# CH1_CH2.net
KiCad netlist of a schematic drawn in Altium Designer
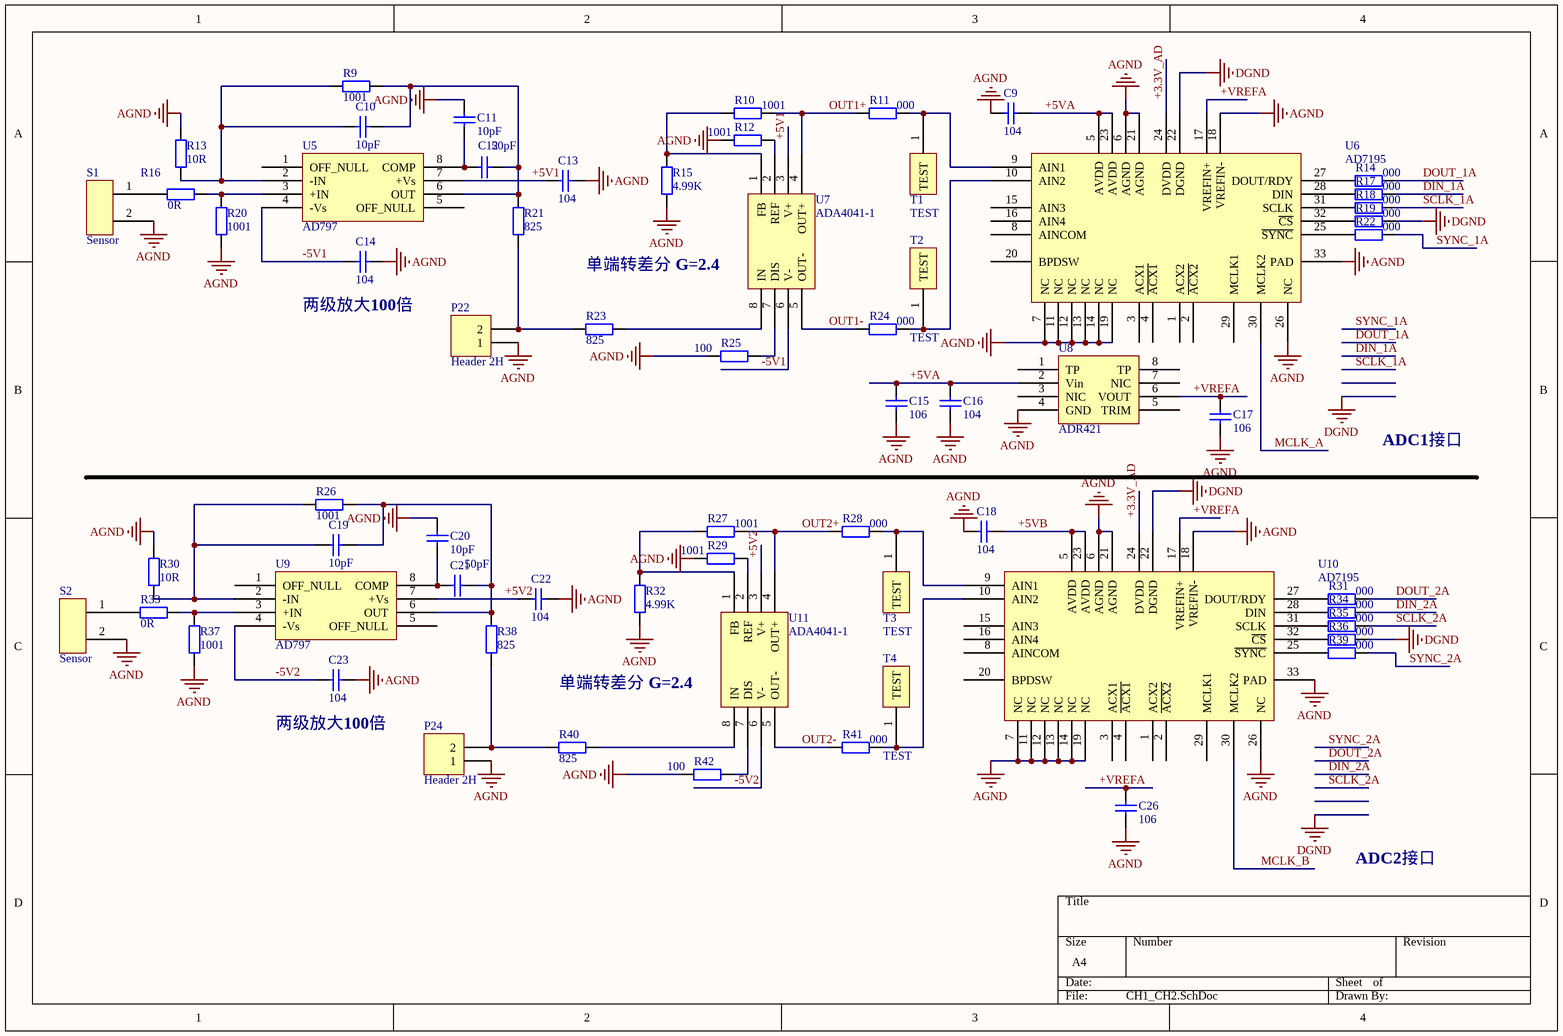
[diagram p0: CH1_CH2.SchDoc]

(export (version "E")
  (design (tool "Eeschema 10.0.6"))
  (components
    (comp (ref "C9")
      (value "104")
      (footprint "0603")
      (description "Capacitor")
      (fields (field (name "PUBLISHER") "Altium Limited"))
      (libsource (lib "Miscellaneous Devices") (part "Cap"))
    )
    (comp (ref "C10")
      (value "10pF")
      (footprint "0603")
      (description "Capacitor")
      (fields (field (name "PUBLISHER") "Altium Limited"))
      (libsource (lib "Miscellaneous Devices") (part "Cap"))
    )
    (comp (ref "C11")
      (value "10pF")
      (footprint "0603")
      (description "Capacitor")
      (fields (field (name "PUBLISHER") "Altium Limited"))
      (libsource (lib "Miscellaneous Devices") (part "Cap"))
    )
    (comp (ref "C12")
      (value "50pF")
      (footprint "0603")
      (description "Capacitor")
      (fields (field (name "PUBLISHER") "Altium Limited"))
      (libsource (lib "Miscellaneous Devices") (part "Cap"))
    )
    (comp (ref "C13")
      (value "104")
      (footprint "0603")
      (description "Capacitor")
      (fields (field (name "PUBLISHER") "Altium Limited"))
      (libsource (lib "Miscellaneous Devices") (part "Cap"))
    )
    (comp (ref "C14")
      (value "104")
      (footprint "0603")
      (description "Capacitor")
      (fields (field (name "PUBLISHER") "Altium Limited"))
      (libsource (lib "Miscellaneous Devices") (part "Cap"))
    )
    (comp (ref "C15")
      (value "106")
      (footprint "0603")
      (description "Capacitor")
      (fields (field (name "PUBLISHER") "Altium Limited"))
      (libsource (lib "Miscellaneous Devices") (part "Cap"))
    )
    (comp (ref "C16")
      (value "104")
      (footprint "0603")
      (description "Capacitor")
      (fields (field (name "PUBLISHER") "Altium Limited"))
      (libsource (lib "Miscellaneous Devices") (part "Cap"))
    )
    (comp (ref "C17")
      (value "106")
      (footprint "0603")
      (description "Capacitor")
      (fields (field (name "PUBLISHER") "Altium Limited"))
      (libsource (lib "Miscellaneous Devices") (part "Cap"))
    )
    (comp (ref "C18")
      (value "104")
      (footprint "0603")
      (description "Capacitor")
      (fields (field (name "PUBLISHER") "Altium Limited"))
      (libsource (lib "Miscellaneous Devices") (part "Cap"))
    )
    (comp (ref "C19")
      (value "10pF")
      (footprint "0603")
      (description "Capacitor")
      (fields (field (name "PUBLISHER") "Altium Limited"))
      (libsource (lib "Miscellaneous Devices") (part "Cap"))
    )
    (comp (ref "C20")
      (value "10pF")
      (footprint "0603")
      (description "Capacitor")
      (fields (field (name "PUBLISHER") "Altium Limited"))
      (libsource (lib "Miscellaneous Devices") (part "Cap"))
    )
    (comp (ref "C21")
      (value "50pF")
      (footprint "0603")
      (description "Capacitor")
      (fields (field (name "PUBLISHER") "Altium Limited"))
      (libsource (lib "Miscellaneous Devices") (part "Cap"))
    )
    (comp (ref "C22")
      (value "104")
      (footprint "0603")
      (description "Capacitor")
      (fields (field (name "PUBLISHER") "Altium Limited"))
      (libsource (lib "Miscellaneous Devices") (part "Cap"))
    )
    (comp (ref "C23")
      (value "104")
      (footprint "0603")
      (description "Capacitor")
      (fields (field (name "PUBLISHER") "Altium Limited"))
      (libsource (lib "Miscellaneous Devices") (part "Cap"))
    )
    (comp (ref "C26")
      (value "106")
      (footprint "0603")
      (description "Capacitor")
      (fields (field (name "PUBLISHER") "Altium Limited"))
      (libsource (lib "Miscellaneous Devices") (part "Cap"))
    )
    (comp (ref "P22")
      (value "Header 2H")
      (footprint "HDR1X2")
      (description "Header, 2-Pin, Right Angle")
      (fields (field (name "PUBLISHER") "Altium Limited"))
      (libsource (lib "Miscellaneous Connectors") (part "Header 2H"))
    )
    (comp (ref "P24")
      (value "Header 2H")
      (footprint "HDR1X2")
      (description "Header, 2-Pin, Right Angle")
      (fields (field (name "PUBLISHER") "Altium Limited"))
      (libsource (lib "Miscellaneous Connectors") (part "Header 2H"))
    )
    (comp (ref "R9")
      (value "1001")
      (footprint "0603")
      (description "Resistor")
      (fields (field (name "PUBLISHER") "Altium Limited"))
      (libsource (lib "Miscellaneous Devices") (part "Res2"))
    )
    (comp (ref "R10")
      (value "1001")
      (footprint "0603")
      (description "Resistor")
      (fields (field (name "PUBLISHER") "Altium Limited"))
      (libsource (lib "Miscellaneous Devices") (part "Res2"))
    )
    (comp (ref "R11")
      (value "000")
      (footprint "0603")
      (description "Resistor")
      (fields (field (name "PUBLISHER") "Altium Limited"))
      (libsource (lib "Miscellaneous Devices") (part "Res2"))
    )
    (comp (ref "R12")
      (value "1001")
      (footprint "0603")
      (description "Resistor")
      (fields (field (name "PUBLISHER") "Altium Limited"))
      (libsource (lib "Miscellaneous Devices") (part "Res2"))
    )
    (comp (ref "R13")
      (value "10R")
      (footprint "0603")
      (description "Resistor")
      (fields (field (name "PUBLISHER") "Altium Limited"))
      (libsource (lib "") (part "Res2_1"))
    )
    (comp (ref "R14")
      (value "000")
      (footprint "0603")
      (description "Resistor")
      (fields (field (name "PUBLISHER") "Altium Limited"))
      (libsource (lib "Miscellaneous Devices") (part "Res2"))
    )
    (comp (ref "R15")
      (value "4.99K")
      (footprint "0603")
      (description "Resistor")
      (fields (field (name "PUBLISHER") "Altium Limited"))
      (libsource (lib "") (part "Res2_2"))
    )
    (comp (ref "R16")
      (value "0R")
      (footprint "0603")
      (description "Resistor")
      (fields (field (name "PUBLISHER") "Altium Limited"))
      (libsource (lib "Miscellaneous Devices") (part "Res2"))
    )
    (comp (ref "R17")
      (value "000")
      (footprint "0603")
      (description "Resistor")
      (fields (field (name "PUBLISHER") "Altium Limited"))
      (libsource (lib "Miscellaneous Devices") (part "Res2"))
    )
    (comp (ref "R18")
      (value "000")
      (footprint "0603")
      (description "Resistor")
      (fields (field (name "PUBLISHER") "Altium Limited"))
      (libsource (lib "Miscellaneous Devices") (part "Res2"))
    )
    (comp (ref "R19")
      (value "000")
      (footprint "0603")
      (description "Resistor")
      (fields (field (name "PUBLISHER") "Altium Limited"))
      (libsource (lib "Miscellaneous Devices") (part "Res2"))
    )
    (comp (ref "R20")
      (value "1001")
      (footprint "0603")
      (description "Resistor")
      (fields (field (name "PUBLISHER") "Altium Limited"))
      (libsource (lib "") (part "Res2_2"))
    )
    (comp (ref "R21")
      (value "825")
      (footprint "0603")
      (description "Resistor")
      (fields (field (name "PUBLISHER") "Altium Limited"))
      (libsource (lib "") (part "Res2_2"))
    )
    (comp (ref "R22")
      (value "000")
      (footprint "0603")
      (description "Resistor")
      (fields (field (name "PUBLISHER") "Altium Limited"))
      (libsource (lib "Miscellaneous Devices") (part "Res2"))
    )
    (comp (ref "R23")
      (value "825")
      (footprint "0603")
      (description "Resistor")
      (fields (field (name "PUBLISHER") "Altium Limited"))
      (libsource (lib "Miscellaneous Devices") (part "Res2"))
    )
    (comp (ref "R24")
      (value "000")
      (footprint "0603")
      (description "Resistor")
      (fields (field (name "PUBLISHER") "Altium Limited"))
      (libsource (lib "Miscellaneous Devices") (part "Res2"))
    )
    (comp (ref "R25")
      (value "100")
      (footprint "0603")
      (description "Resistor")
      (fields (field (name "PUBLISHER") "Altium Limited"))
      (libsource (lib "Miscellaneous Devices") (part "Res2"))
    )
    (comp (ref "R26")
      (value "1001")
      (footprint "0603")
      (description "Resistor")
      (fields (field (name "PUBLISHER") "Altium Limited"))
      (libsource (lib "Miscellaneous Devices") (part "Res2"))
    )
    (comp (ref "R27")
      (value "1001")
      (footprint "0603")
      (description "Resistor")
      (fields (field (name "PUBLISHER") "Altium Limited"))
      (libsource (lib "Miscellaneous Devices") (part "Res2"))
    )
    (comp (ref "R28")
      (value "000")
      (footprint "0603")
      (description "Resistor")
      (fields (field (name "PUBLISHER") "Altium Limited"))
      (libsource (lib "Miscellaneous Devices") (part "Res2"))
    )
    (comp (ref "R29")
      (value "1001")
      (footprint "0603")
      (description "Resistor")
      (fields (field (name "PUBLISHER") "Altium Limited"))
      (libsource (lib "Miscellaneous Devices") (part "Res2"))
    )
    (comp (ref "R30")
      (value "10R")
      (footprint "0603")
      (description "Resistor")
      (fields (field (name "PUBLISHER") "Altium Limited"))
      (libsource (lib "") (part "Res2_1"))
    )
    (comp (ref "R31")
      (value "000")
      (footprint "0603")
      (description "Resistor")
      (fields (field (name "PUBLISHER") "Altium Limited"))
      (libsource (lib "Miscellaneous Devices") (part "Res2"))
    )
    (comp (ref "R32")
      (value "4.99K")
      (footprint "0603")
      (description "Resistor")
      (fields (field (name "PUBLISHER") "Altium Limited"))
      (libsource (lib "") (part "Res2_2"))
    )
    (comp (ref "R33")
      (value "0R")
      (footprint "0603")
      (description "Resistor")
      (fields (field (name "PUBLISHER") "Altium Limited"))
      (libsource (lib "Miscellaneous Devices") (part "Res2"))
    )
    (comp (ref "R34")
      (value "000")
      (footprint "0603")
      (description "Resistor")
      (fields (field (name "PUBLISHER") "Altium Limited"))
      (libsource (lib "Miscellaneous Devices") (part "Res2"))
    )
    (comp (ref "R35")
      (value "000")
      (footprint "0603")
      (description "Resistor")
      (fields (field (name "PUBLISHER") "Altium Limited"))
      (libsource (lib "Miscellaneous Devices") (part "Res2"))
    )
    (comp (ref "R36")
      (value "000")
      (footprint "0603")
      (description "Resistor")
      (fields (field (name "PUBLISHER") "Altium Limited"))
      (libsource (lib "Miscellaneous Devices") (part "Res2"))
    )
    (comp (ref "R37")
      (value "1001")
      (footprint "0603")
      (description "Resistor")
      (fields (field (name "PUBLISHER") "Altium Limited"))
      (libsource (lib "") (part "Res2_2"))
    )
    (comp (ref "R38")
      (value "825")
      (footprint "0603")
      (description "Resistor")
      (fields (field (name "PUBLISHER") "Altium Limited"))
      (libsource (lib "") (part "Res2_2"))
    )
    (comp (ref "R39")
      (value "000")
      (footprint "0603")
      (description "Resistor")
      (fields (field (name "PUBLISHER") "Altium Limited"))
      (libsource (lib "Miscellaneous Devices") (part "Res2"))
    )
    (comp (ref "R40")
      (value "825")
      (footprint "0603")
      (description "Resistor")
      (fields (field (name "PUBLISHER") "Altium Limited"))
      (libsource (lib "Miscellaneous Devices") (part "Res2"))
    )
    (comp (ref "R41")
      (value "000")
      (footprint "0603")
      (description "Resistor")
      (fields (field (name "PUBLISHER") "Altium Limited"))
      (libsource (lib "Miscellaneous Devices") (part "Res2"))
    )
    (comp (ref "R42")
      (value "100")
      (footprint "0603")
      (description "Resistor")
      (fields (field (name "PUBLISHER") "Altium Limited"))
      (libsource (lib "Miscellaneous Devices") (part "Res2"))
    )
    (comp (ref "S1") (value "Sensor") (footprint "HDR1X2") (libsource (lib "Schlib1") (part "Sensor")))
    (comp (ref "S2") (value "Sensor") (footprint "HDR1X2") (libsource (lib "Schlib1") (part "Sensor")))
    (comp (ref "T1") (value "TEST") (footprint "TEST") (libsource (lib "Schlib1") (part "TEST")))
    (comp (ref "T2") (value "TEST") (footprint "TEST") (libsource (lib "") (part "TEST_1")))
    (comp (ref "T3") (value "TEST") (footprint "TEST") (libsource (lib "Schlib1") (part "TEST")))
    (comp (ref "T4") (value "TEST") (footprint "TEST") (libsource (lib "") (part "TEST_1")))
    (comp (ref "U5") (value "AD797") (footprint "SO8") (libsource (lib "Schlib1") (part "AD797")))
    (comp (ref "U6") (value "AD7195") (footprint "VQFN32") (libsource (lib "Schlib1") (part "AD7195")))
    (comp (ref "U7") (value "ADA4041-1") (footprint "SO8") (libsource (lib "Schlib1") (part "ADA4041-1")))
    (comp (ref "U8") (value "ADR421") (footprint "SO8") (libsource (lib "Schlib1") (part "ADR421")))
    (comp (ref "U9") (value "AD797") (footprint "SO8") (libsource (lib "Schlib1") (part "AD797")))
    (comp (ref "U10") (value "AD7195") (footprint "VQFN32") (libsource (lib "Schlib1") (part "AD7195")))
    (comp (ref "U11") (value "ADA4041-1") (footprint "SO8") (libsource (lib "Schlib1") (part "ADA4041-1")))
  )
  (nets
    (net (code "1") (name "/+3.3V_AD") (class "Default")
      (node (ref "U10") (pin "24") (pinfunction "DVDD_24") (pintype "passive"))
      (node (ref "U6") (pin "24") (pinfunction "DVDD_24") (pintype "passive"))
    )
    (net (code "2") (name "/+5V1") (class "Default")
      (node (ref "C13") (pin "2") (pinfunction "2_2") (pintype "passive"))
      (node (ref "U5") (pin "7") (pinfunction "+Vs_7") (pintype "passive"))
      (node (ref "U7") (pin "3") (pinfunction "V+_3") (pintype "passive"))
    )
    (net (code "3") (name "/+5V2") (class "Default")
      (node (ref "C22") (pin "2") (pinfunction "2_2") (pintype "passive"))
      (node (ref "U11") (pin "3") (pinfunction "V+_3") (pintype "passive"))
      (node (ref "U9") (pin "7") (pinfunction "+Vs_7") (pintype "passive"))
    )
    (net (code "4") (name "/+5VA") (class "Default")
      (node (ref "C15") (pin "1") (pinfunction "1_1") (pintype "passive"))
      (node (ref "C16") (pin "1") (pinfunction "1_1") (pintype "passive"))
      (node (ref "C9") (pin "2") (pinfunction "2_2") (pintype "passive"))
      (node (ref "U6") (pin "23") (pinfunction "AVDD_23") (pintype "passive"))
      (node (ref "U6") (pin "5") (pinfunction "AVDD_5") (pintype "passive"))
      (node (ref "U8") (pin "2") (pinfunction "Vin_2") (pintype "passive"))
    )
    (net (code "5") (name "/+5VB") (class "Default")
      (node (ref "C18") (pin "2") (pinfunction "2_2") (pintype "passive"))
      (node (ref "U10") (pin "23") (pinfunction "AVDD_23") (pintype "passive"))
      (node (ref "U10") (pin "5") (pinfunction "AVDD_5") (pintype "passive"))
    )
    (net (code "6") (name "/+VREFA") (class "Default")
      (node (ref "C17") (pin "1") (pinfunction "1_1") (pintype "passive"))
      (node (ref "C26") (pin "1") (pinfunction "1_1") (pintype "passive"))
      (node (ref "U10") (pin "17") (pinfunction "VREFIN+_17") (pintype "passive"))
      (node (ref "U6") (pin "17") (pinfunction "VREFIN+_17") (pintype "passive"))
      (node (ref "U8") (pin "6") (pinfunction "VOUT_6") (pintype "passive"))
    )
    (net (code "7") (name "/-5V1") (class "Default")
      (node (ref "C14") (pin "2") (pinfunction "2_2") (pintype "passive"))
      (node (ref "U5") (pin "4") (pinfunction "-Vs_4") (pintype "passive"))
      (node (ref "U7") (pin "6") (pinfunction "V-_6") (pintype "passive"))
    )
    (net (code "8") (name "/-5V2") (class "Default")
      (node (ref "C23") (pin "2") (pinfunction "2_2") (pintype "passive"))
      (node (ref "U11") (pin "6") (pinfunction "V-_6") (pintype "passive"))
      (node (ref "U9") (pin "4") (pinfunction "-Vs_4") (pintype "passive"))
    )
    (net (code "9") (name "/DIN_1A") (class "Default")
      (node (ref "R17") (pin "2") (pinfunction "2_2") (pintype "passive"))
    )
    (net (code "10") (name "/DIN_2A") (class "Default")
      (node (ref "R34") (pin "2") (pinfunction "2_2") (pintype "passive"))
    )
    (net (code "11") (name "/DOUT_1A") (class "Default")
      (node (ref "R14") (pin "2") (pinfunction "2_2") (pintype "passive"))
    )
    (net (code "12") (name "/DOUT_2A") (class "Default")
      (node (ref "R31") (pin "2") (pinfunction "2_2") (pintype "passive"))
    )
    (net (code "13") (name "/MCLK_A") (class "Default")
      (node (ref "U6") (pin "30") (pinfunction "MCLK2_30") (pintype "passive"))
    )
    (net (code "14") (name "/MCLK_B") (class "Default")
      (node (ref "U10") (pin "30") (pinfunction "MCLK2_30") (pintype "passive"))
    )
    (net (code "15") (name "/OUT1+") (class "Default")
      (node (ref "R10") (pin "2") (pinfunction "2_2") (pintype "passive"))
      (node (ref "R11") (pin "1") (pinfunction "1_1") (pintype "passive"))
      (node (ref "U7") (pin "4") (pinfunction "OUT+_4") (pintype "passive"))
    )
    (net (code "16") (name "/OUT1-") (class "Default")
      (node (ref "R24") (pin "1") (pinfunction "1_1") (pintype "passive"))
      (node (ref "U7") (pin "5") (pinfunction "OUT-_5") (pintype "passive"))
    )
    (net (code "17") (name "/OUT2+") (class "Default")
      (node (ref "R27") (pin "2") (pinfunction "2_2") (pintype "passive"))
      (node (ref "R28") (pin "1") (pinfunction "1_1") (pintype "passive"))
      (node (ref "U11") (pin "4") (pinfunction "OUT+_4") (pintype "passive"))
    )
    (net (code "18") (name "/OUT2-") (class "Default")
      (node (ref "R41") (pin "1") (pinfunction "1_1") (pintype "passive"))
      (node (ref "U11") (pin "5") (pinfunction "OUT-_5") (pintype "passive"))
    )
    (net (code "19") (name "/SCLK_1A") (class "Default")
      (node (ref "R18") (pin "2") (pinfunction "2_2") (pintype "passive"))
    )
    (net (code "20") (name "/SCLK_2A") (class "Default")
      (node (ref "R35") (pin "2") (pinfunction "2_2") (pintype "passive"))
    )
    (net (code "21") (name "/SYNC_1A") (class "Default")
      (node (ref "R22") (pin "2") (pinfunction "2_2") (pintype "passive"))
    )
    (net (code "22") (name "/SYNC_2A") (class "Default")
      (node (ref "R39") (pin "2") (pinfunction "2_2") (pintype "passive"))
    )
    (net (code "23") (name "AGND") (class "Default")
      (node (ref "C11") (pin "2") (pinfunction "2_2") (pintype "passive"))
      (node (ref "C13") (pin "1") (pinfunction "1_1") (pintype "passive"))
      (node (ref "C14") (pin "1") (pinfunction "1_1") (pintype "passive"))
      (node (ref "C15") (pin "2") (pinfunction "2_2") (pintype "passive"))
      (node (ref "C16") (pin "2") (pinfunction "2_2") (pintype "passive"))
      (node (ref "C17") (pin "2") (pinfunction "2_2") (pintype "passive"))
      (node (ref "C18") (pin "1") (pinfunction "1_1") (pintype "passive"))
      (node (ref "C20") (pin "2") (pinfunction "2_2") (pintype "passive"))
      (node (ref "C22") (pin "1") (pinfunction "1_1") (pintype "passive"))
      (node (ref "C23") (pin "1") (pinfunction "1_1") (pintype "passive"))
      (node (ref "C26") (pin "2") (pinfunction "2_2") (pintype "passive"))
      (node (ref "C9") (pin "1") (pinfunction "1_1") (pintype "passive"))
      (node (ref "P22") (pin "1") (pinfunction "1_1") (pintype "passive"))
      (node (ref "P24") (pin "1") (pinfunction "1_1") (pintype "passive"))
      (node (ref "R12") (pin "1") (pinfunction "1_1") (pintype "passive"))
      (node (ref "R13") (pin "1") (pinfunction "1_1") (pintype "passive"))
      (node (ref "R15") (pin "1") (pinfunction "1_1") (pintype "passive"))
      (node (ref "R20") (pin "1") (pinfunction "1_1") (pintype "passive"))
      (node (ref "R25") (pin "1") (pinfunction "1_1") (pintype "passive"))
      (node (ref "R29") (pin "1") (pinfunction "1_1") (pintype "passive"))
      (node (ref "R30") (pin "1") (pinfunction "1_1") (pintype "passive"))
      (node (ref "R32") (pin "1") (pinfunction "1_1") (pintype "passive"))
      (node (ref "R37") (pin "1") (pinfunction "1_1") (pintype "passive"))
      (node (ref "R42") (pin "1") (pinfunction "1_1") (pintype "passive"))
      (node (ref "S1") (pin "2") (pinfunction "2_2") (pintype "passive"))
      (node (ref "S2") (pin "2") (pinfunction "2_2") (pintype "passive"))
      (node (ref "U10") (pin "11") (pinfunction "NC_11") (pintype "passive"))
      (node (ref "U10") (pin "12") (pinfunction "NC_12") (pintype "passive"))
      (node (ref "U10") (pin "13") (pinfunction "NC_13") (pintype "passive"))
      (node (ref "U10") (pin "14") (pinfunction "NC_14") (pintype "passive"))
      (node (ref "U10") (pin "18") (pinfunction "VREFIN-_18") (pintype "passive"))
      (node (ref "U10") (pin "19") (pinfunction "NC_19") (pintype "passive"))
      (node (ref "U10") (pin "21") (pinfunction "AGND_21") (pintype "passive"))
      (node (ref "U10") (pin "26") (pinfunction "NC_26") (pintype "passive"))
      (node (ref "U10") (pin "33") (pinfunction "PAD_33") (pintype "passive"))
      (node (ref "U10") (pin "6") (pinfunction "AGND_6") (pintype "passive"))
      (node (ref "U10") (pin "7") (pinfunction "NC_7") (pintype "passive"))
      (node (ref "U6") (pin "11") (pinfunction "NC_11") (pintype "passive"))
      (node (ref "U6") (pin "12") (pinfunction "NC_12") (pintype "passive"))
      (node (ref "U6") (pin "13") (pinfunction "NC_13") (pintype "passive"))
      (node (ref "U6") (pin "14") (pinfunction "NC_14") (pintype "passive"))
      (node (ref "U6") (pin "18") (pinfunction "VREFIN-_18") (pintype "passive"))
      (node (ref "U6") (pin "19") (pinfunction "NC_19") (pintype "passive"))
      (node (ref "U6") (pin "21") (pinfunction "AGND_21") (pintype "passive"))
      (node (ref "U6") (pin "26") (pinfunction "NC_26") (pintype "passive"))
      (node (ref "U6") (pin "33") (pinfunction "PAD_33") (pintype "passive"))
      (node (ref "U6") (pin "6") (pinfunction "AGND_6") (pintype "passive"))
      (node (ref "U6") (pin "7") (pinfunction "NC_7") (pintype "passive"))
      (node (ref "U8") (pin "4") (pinfunction "GND_4") (pintype "passive"))
    )
    (net (code "24") (name "DGND") (class "Default")
      (node (ref "R19") (pin "2") (pinfunction "2_2") (pintype "passive"))
      (node (ref "R36") (pin "2") (pinfunction "2_2") (pintype "passive"))
      (node (ref "U10") (pin "22") (pinfunction "DGND_22") (pintype "passive"))
      (node (ref "U6") (pin "22") (pinfunction "DGND_22") (pintype "passive"))
    )
    (net (code "25") (name "Net-(P22-Pad2)") (class "Default")
      (node (ref "P22") (pin "2") (pinfunction "2_2") (pintype "passive"))
      (node (ref "R21") (pin "1") (pinfunction "1_1") (pintype "passive"))
      (node (ref "R23") (pin "1") (pinfunction "1_1") (pintype "passive"))
    )
    (net (code "26") (name "Net-(P24-Pad2)") (class "Default")
      (node (ref "P24") (pin "2") (pinfunction "2_2") (pintype "passive"))
      (node (ref "R38") (pin "1") (pinfunction "1_1") (pintype "passive"))
      (node (ref "R40") (pin "1") (pinfunction "1_1") (pintype "passive"))
    )
    (net (code "27") (name "Net-(R16-Pad1)") (class "Default")
      (node (ref "R16") (pin "1") (pinfunction "1_1") (pintype "passive"))
      (node (ref "S1") (pin "1") (pinfunction "1_1") (pintype "passive"))
    )
    (net (code "28") (name "Net-(R33-Pad1)") (class "Default")
      (node (ref "R33") (pin "1") (pinfunction "1_1") (pintype "passive"))
      (node (ref "S2") (pin "1") (pinfunction "1_1") (pintype "passive"))
    )
    (net (code "29") (name "Net-(T1-TEST)") (class "Default")
      (node (ref "R11") (pin "2") (pinfunction "2_2") (pintype "passive"))
      (node (ref "T1") (pin "1") (pinfunction "TEST_1") (pintype "passive"))
      (node (ref "U6") (pin "9") (pinfunction "AIN1_9") (pintype "passive"))
    )
    (net (code "30") (name "Net-(T2-TEST)") (class "Default")
      (node (ref "R24") (pin "2") (pinfunction "2_2") (pintype "passive"))
      (node (ref "T2") (pin "1") (pinfunction "TEST_1") (pintype "passive"))
      (node (ref "U6") (pin "10") (pinfunction "AIN2_10") (pintype "passive"))
    )
    (net (code "31") (name "Net-(T3-TEST)") (class "Default")
      (node (ref "R28") (pin "2") (pinfunction "2_2") (pintype "passive"))
      (node (ref "T3") (pin "1") (pinfunction "TEST_1") (pintype "passive"))
      (node (ref "U10") (pin "9") (pinfunction "AIN1_9") (pintype "passive"))
    )
    (net (code "32") (name "Net-(T4-TEST)") (class "Default")
      (node (ref "R41") (pin "2") (pinfunction "2_2") (pintype "passive"))
      (node (ref "T4") (pin "1") (pinfunction "TEST_1") (pintype "passive"))
      (node (ref "U10") (pin "10") (pinfunction "AIN2_10") (pintype "passive"))
    )
    (net (code "33") (name "Net-(U5-+IN)") (class "Default")
      (node (ref "R16") (pin "2") (pinfunction "2_2") (pintype "passive"))
      (node (ref "R20") (pin "2") (pinfunction "2_2") (pintype "passive"))
      (node (ref "U5") (pin "3") (pinfunction "+IN_3") (pintype "passive"))
    )
    (net (code "34") (name "Net-(U5--IN)") (class "Default")
      (node (ref "C10") (pin "2") (pinfunction "2_2") (pintype "passive"))
      (node (ref "R13") (pin "2") (pinfunction "2_2") (pintype "passive"))
      (node (ref "R9") (pin "1") (pinfunction "1_1") (pintype "passive"))
      (node (ref "U5") (pin "2") (pinfunction "-IN_2") (pintype "passive"))
    )
    (net (code "35") (name "Net-(U5-COMP)") (class "Default")
      (node (ref "C11") (pin "1") (pinfunction "1_1") (pintype "passive"))
      (node (ref "C12") (pin "2") (pinfunction "2_2") (pintype "passive"))
      (node (ref "U5") (pin "8") (pinfunction "COMP_8") (pintype "passive"))
    )
    (net (code "36") (name "Net-(U5-OUT)") (class "Default")
      (node (ref "C10") (pin "1") (pinfunction "1_1") (pintype "passive"))
      (node (ref "C12") (pin "1") (pinfunction "1_1") (pintype "passive"))
      (node (ref "R21") (pin "2") (pinfunction "2_2") (pintype "passive"))
      (node (ref "R9") (pin "2") (pinfunction "2_2") (pintype "passive"))
      (node (ref "U5") (pin "6") (pinfunction "OUT_6") (pintype "passive"))
    )
    (net (code "37") (name "Net-(U6-DIN)") (class "Default")
      (node (ref "R17") (pin "1") (pinfunction "1_1") (pintype "passive"))
      (node (ref "U6") (pin "28") (pinfunction "DIN_28") (pintype "passive"))
    )
    (net (code "38") (name "Net-(U6-DOUT{slash}RDY)") (class "Default")
      (node (ref "R14") (pin "1") (pinfunction "1_1") (pintype "passive"))
      (node (ref "U6") (pin "27") (pinfunction "DOUT/RDY_27") (pintype "passive"))
    )
    (net (code "39") (name "Net-(U6-SCLK)") (class "Default")
      (node (ref "R18") (pin "1") (pinfunction "1_1") (pintype "passive"))
      (node (ref "U6") (pin "31") (pinfunction "SCLK_31") (pintype "passive"))
    )
    (net (code "40") (name "Net-(U6-~{CS})") (class "Default")
      (node (ref "R19") (pin "1") (pinfunction "1_1") (pintype "passive"))
      (node (ref "U6") (pin "32") (pinfunction "~{CS}_32") (pintype "passive"))
    )
    (net (code "41") (name "Net-(U6-~{SYNC})") (class "Default")
      (node (ref "R22") (pin "1") (pinfunction "1_1") (pintype "passive"))
      (node (ref "U6") (pin "25") (pinfunction "~{SYNC}_25") (pintype "passive"))
    )
    (net (code "42") (name "Net-(U7-DIS)") (class "Default")
      (node (ref "R25") (pin "2") (pinfunction "2_2") (pintype "passive"))
      (node (ref "U7") (pin "7") (pinfunction "DIS_7") (pintype "passive"))
    )
    (net (code "43") (name "Net-(U7-FB)") (class "Default")
      (node (ref "R10") (pin "1") (pinfunction "1_1") (pintype "passive"))
      (node (ref "R15") (pin "2") (pinfunction "2_2") (pintype "passive"))
      (node (ref "U7") (pin "1") (pinfunction "FB_1") (pintype "passive"))
    )
    (net (code "44") (name "Net-(U7-IN)") (class "Default")
      (node (ref "R23") (pin "2") (pinfunction "2_2") (pintype "passive"))
      (node (ref "U7") (pin "8") (pinfunction "IN_8") (pintype "passive"))
    )
    (net (code "45") (name "Net-(U7-REF)") (class "Default")
      (node (ref "R12") (pin "2") (pinfunction "2_2") (pintype "passive"))
      (node (ref "U7") (pin "2") (pinfunction "REF_2") (pintype "passive"))
    )
    (net (code "46") (name "Net-(U9-+IN)") (class "Default")
      (node (ref "R33") (pin "2") (pinfunction "2_2") (pintype "passive"))
      (node (ref "R37") (pin "2") (pinfunction "2_2") (pintype "passive"))
      (node (ref "U9") (pin "3") (pinfunction "+IN_3") (pintype "passive"))
    )
    (net (code "47") (name "Net-(U9--IN)") (class "Default")
      (node (ref "C19") (pin "2") (pinfunction "2_2") (pintype "passive"))
      (node (ref "R26") (pin "1") (pinfunction "1_1") (pintype "passive"))
      (node (ref "R30") (pin "2") (pinfunction "2_2") (pintype "passive"))
      (node (ref "U9") (pin "2") (pinfunction "-IN_2") (pintype "passive"))
    )
    (net (code "48") (name "Net-(U9-COMP)") (class "Default")
      (node (ref "C20") (pin "1") (pinfunction "1_1") (pintype "passive"))
      (node (ref "C21") (pin "2") (pinfunction "2_2") (pintype "passive"))
      (node (ref "U9") (pin "8") (pinfunction "COMP_8") (pintype "passive"))
    )
    (net (code "49") (name "Net-(U9-OUT)") (class "Default")
      (node (ref "C19") (pin "1") (pinfunction "1_1") (pintype "passive"))
      (node (ref "C21") (pin "1") (pinfunction "1_1") (pintype "passive"))
      (node (ref "R26") (pin "2") (pinfunction "2_2") (pintype "passive"))
      (node (ref "R38") (pin "2") (pinfunction "2_2") (pintype "passive"))
      (node (ref "U9") (pin "6") (pinfunction "OUT_6") (pintype "passive"))
    )
    (net (code "50") (name "Net-(U10-DIN)") (class "Default")
      (node (ref "R34") (pin "1") (pinfunction "1_1") (pintype "passive"))
      (node (ref "U10") (pin "28") (pinfunction "DIN_28") (pintype "passive"))
    )
    (net (code "51") (name "Net-(U10-DOUT{slash}RDY)") (class "Default")
      (node (ref "R31") (pin "1") (pinfunction "1_1") (pintype "passive"))
      (node (ref "U10") (pin "27") (pinfunction "DOUT/RDY_27") (pintype "passive"))
    )
    (net (code "52") (name "Net-(U10-SCLK)") (class "Default")
      (node (ref "R35") (pin "1") (pinfunction "1_1") (pintype "passive"))
      (node (ref "U10") (pin "31") (pinfunction "SCLK_31") (pintype "passive"))
    )
    (net (code "53") (name "Net-(U10-~{CS})") (class "Default")
      (node (ref "R36") (pin "1") (pinfunction "1_1") (pintype "passive"))
      (node (ref "U10") (pin "32") (pinfunction "~{CS}_32") (pintype "passive"))
    )
    (net (code "54") (name "Net-(U10-~{SYNC})") (class "Default")
      (node (ref "R39") (pin "1") (pinfunction "1_1") (pintype "passive"))
      (node (ref "U10") (pin "25") (pinfunction "~{SYNC}_25") (pintype "passive"))
    )
    (net (code "55") (name "Net-(U11-DIS)") (class "Default")
      (node (ref "R42") (pin "2") (pinfunction "2_2") (pintype "passive"))
      (node (ref "U11") (pin "7") (pinfunction "DIS_7") (pintype "passive"))
    )
    (net (code "56") (name "Net-(U11-FB)") (class "Default")
      (node (ref "R27") (pin "1") (pinfunction "1_1") (pintype "passive"))
      (node (ref "R32") (pin "2") (pinfunction "2_2") (pintype "passive"))
      (node (ref "U11") (pin "1") (pinfunction "FB_1") (pintype "passive"))
    )
    (net (code "57") (name "Net-(U11-IN)") (class "Default")
      (node (ref "R40") (pin "2") (pinfunction "2_2") (pintype "passive"))
      (node (ref "U11") (pin "8") (pinfunction "IN_8") (pintype "passive"))
    )
    (net (code "58") (name "Net-(U11-REF)") (class "Default")
      (node (ref "R29") (pin "2") (pinfunction "2_2") (pintype "passive"))
      (node (ref "U11") (pin "2") (pinfunction "REF_2") (pintype "passive"))
    )
    (net (code "59") (name "unconnected-(U5-OFF_NULL-Pad1)") (class "Default")
      (node (ref "U5") (pin "1") (pinfunction "OFF_NULL_1") (pintype "passive"))
    )
    (net (code "60") (name "unconnected-(U5-OFF_NULL-Pad5)") (class "Default")
      (node (ref "U5") (pin "5") (pinfunction "OFF_NULL_5") (pintype "passive"))
    )
    (net (code "61") (name "unconnected-(U6-ACX1-Pad3)") (class "Default")
      (node (ref "U6") (pin "3") (pinfunction "ACX1_3") (pintype "passive"))
    )
    (net (code "62") (name "unconnected-(U6-ACX2-Pad1)") (class "Default")
      (node (ref "U6") (pin "1") (pinfunction "ACX2_1") (pintype "passive"))
    )
    (net (code "63") (name "unconnected-(U6-AIN3-Pad15)") (class "Default")
      (node (ref "U6") (pin "15") (pinfunction "AIN3_15") (pintype "passive"))
    )
    (net (code "64") (name "unconnected-(U6-AIN4-Pad16)") (class "Default")
      (node (ref "U6") (pin "16") (pinfunction "AIN4_16") (pintype "passive"))
    )
    (net (code "65") (name "unconnected-(U6-AINCOM-Pad8)") (class "Default")
      (node (ref "U6") (pin "8") (pinfunction "AINCOM_8") (pintype "passive"))
    )
    (net (code "66") (name "unconnected-(U6-BPDSW-Pad20)") (class "Default")
      (node (ref "U6") (pin "20") (pinfunction "BPDSW_20") (pintype "passive"))
    )
    (net (code "67") (name "unconnected-(U6-MCLK1-Pad29)") (class "Default")
      (node (ref "U6") (pin "29") (pinfunction "MCLK1_29") (pintype "passive"))
    )
    (net (code "68") (name "unconnected-(U6-~{ACX1}-Pad4)") (class "Default")
      (node (ref "U6") (pin "4") (pinfunction "~{ACX1}_4") (pintype "passive"))
    )
    (net (code "69") (name "unconnected-(U6-~{ACX2}-Pad2)") (class "Default")
      (node (ref "U6") (pin "2") (pinfunction "~{ACX2}_2") (pintype "passive"))
    )
    (net (code "70") (name "unconnected-(U8-NIC-Pad3)") (class "Default")
      (node (ref "U8") (pin "3") (pinfunction "NIC_3") (pintype "passive"))
    )
    (net (code "71") (name "unconnected-(U8-NIC-Pad7)") (class "Default")
      (node (ref "U8") (pin "7") (pinfunction "NIC_7") (pintype "passive"))
    )
    (net (code "72") (name "unconnected-(U8-TP-Pad1)") (class "Default")
      (node (ref "U8") (pin "1") (pinfunction "TP_1") (pintype "passive"))
    )
    (net (code "73") (name "unconnected-(U8-TP-Pad8)") (class "Default")
      (node (ref "U8") (pin "8") (pinfunction "TP_8") (pintype "passive"))
    )
    (net (code "74") (name "unconnected-(U8-TRIM-Pad5)") (class "Default")
      (node (ref "U8") (pin "5") (pinfunction "TRIM_5") (pintype "passive"))
    )
    (net (code "75") (name "unconnected-(U9-OFF_NULL-Pad1)") (class "Default")
      (node (ref "U9") (pin "1") (pinfunction "OFF_NULL_1") (pintype "passive"))
    )
    (net (code "76") (name "unconnected-(U9-OFF_NULL-Pad5)") (class "Default")
      (node (ref "U9") (pin "5") (pinfunction "OFF_NULL_5") (pintype "passive"))
    )
    (net (code "77") (name "unconnected-(U10-ACX1-Pad3)") (class "Default")
      (node (ref "U10") (pin "3") (pinfunction "ACX1_3") (pintype "passive"))
    )
    (net (code "78") (name "unconnected-(U10-ACX2-Pad1)") (class "Default")
      (node (ref "U10") (pin "1") (pinfunction "ACX2_1") (pintype "passive"))
    )
    (net (code "79") (name "unconnected-(U10-AIN3-Pad15)") (class "Default")
      (node (ref "U10") (pin "15") (pinfunction "AIN3_15") (pintype "passive"))
    )
    (net (code "80") (name "unconnected-(U10-AIN4-Pad16)") (class "Default")
      (node (ref "U10") (pin "16") (pinfunction "AIN4_16") (pintype "passive"))
    )
    (net (code "81") (name "unconnected-(U10-AINCOM-Pad8)") (class "Default")
      (node (ref "U10") (pin "8") (pinfunction "AINCOM_8") (pintype "passive"))
    )
    (net (code "82") (name "unconnected-(U10-BPDSW-Pad20)") (class "Default")
      (node (ref "U10") (pin "20") (pinfunction "BPDSW_20") (pintype "passive"))
    )
    (net (code "83") (name "unconnected-(U10-MCLK1-Pad29)") (class "Default")
      (node (ref "U10") (pin "29") (pinfunction "MCLK1_29") (pintype "passive"))
    )
    (net (code "84") (name "unconnected-(U10-~{ACX1}-Pad4)") (class "Default")
      (node (ref "U10") (pin "4") (pinfunction "~{ACX1}_4") (pintype "passive"))
    )
    (net (code "85") (name "unconnected-(U10-~{ACX2}-Pad2)") (class "Default")
      (node (ref "U10") (pin "2") (pinfunction "~{ACX2}_2") (pintype "passive"))
    )
  )
)
